# HyperRAM.net
KiCad netlist of a schematic drawn in Altium Designer
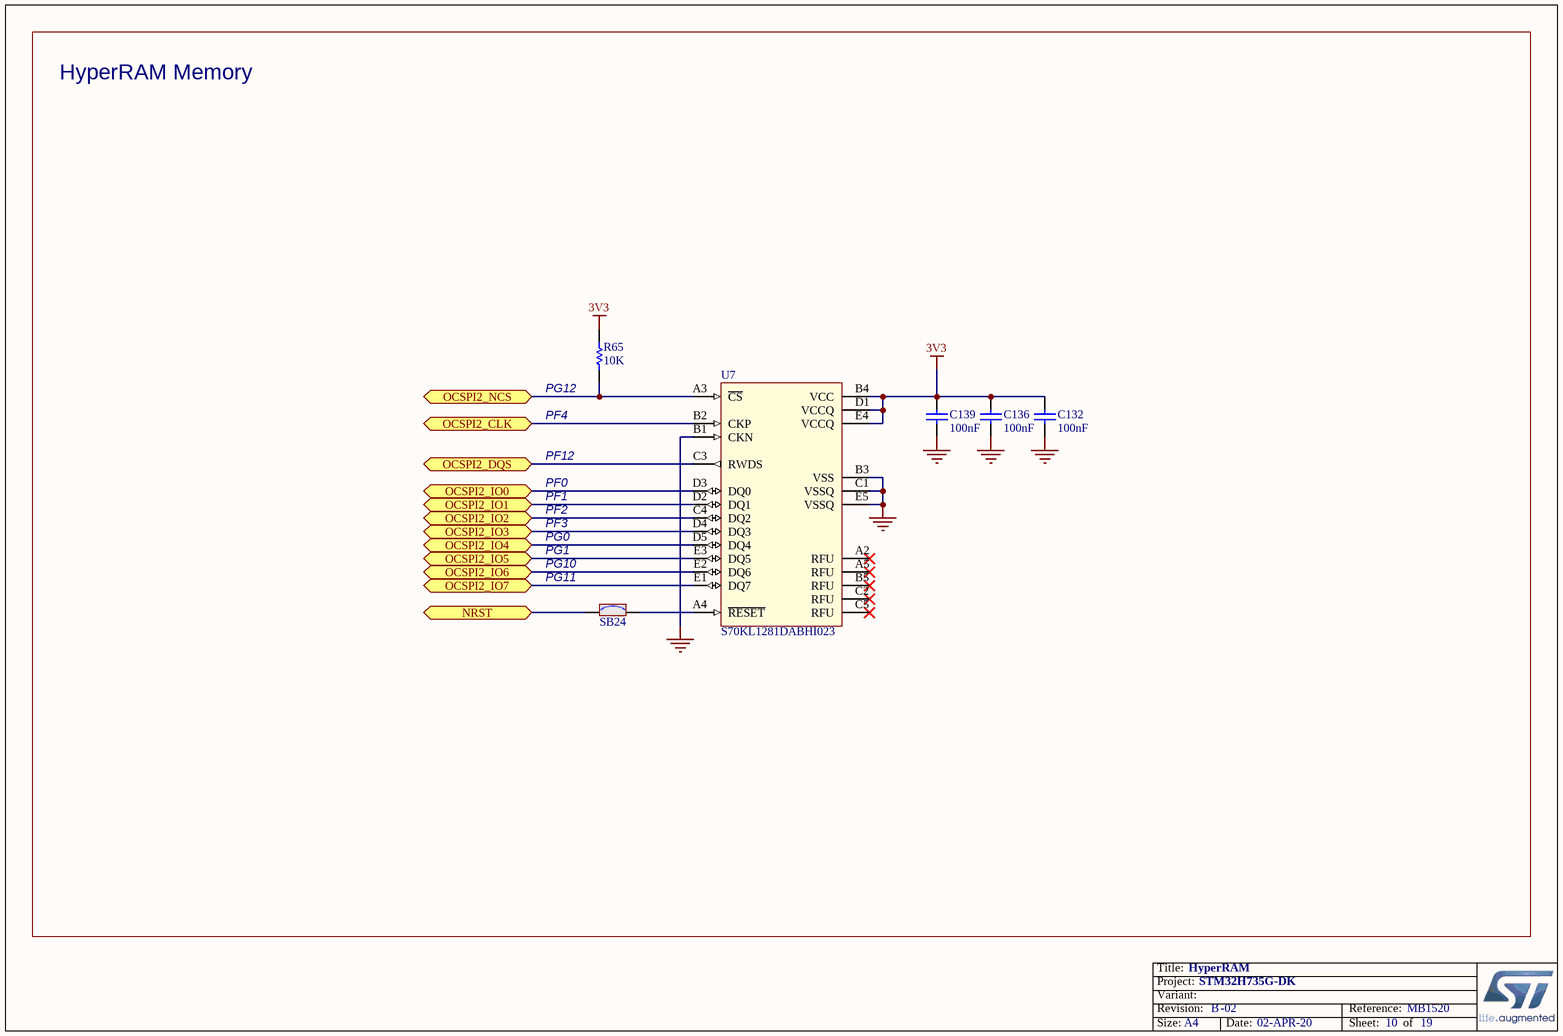
[diagram p0: HyperRAM.SchDoc]

(export (version "E")
  (design (tool "Eeschema 10.0.6"))
  (components
    (comp (ref "C132")
      (value "100nF")
      (footprint "C0402")
      (description "Capacitor, MLCC, 100nF, 16V, X7R, 10%, 0402, T=0,5mm")
      (fields
        (field (name "INTERNAL_PART_NUMBER") "MCD-00102")
        (field (name "MANUFACTURER_PART_NUMBER") "CC0402KRX7R7BB104")
        (field (name "PROVIDED_BY") "SUBCO")
      )
      (libsource (lib "MCD_PARTS_database") (part "Capacitor"))
    )
    (comp (ref "C136")
      (value "100nF")
      (footprint "C0402")
      (description "Capacitor, MLCC, 100nF, 16V, X7R, 10%, 0402, T=0,5mm")
      (fields
        (field (name "INTERNAL_PART_NUMBER") "MCD-00102")
        (field (name "MANUFACTURER_PART_NUMBER") "CC0402KRX7R7BB104")
        (field (name "PROVIDED_BY") "SUBCO")
      )
      (libsource (lib "MCD_PARTS_database") (part "Capacitor"))
    )
    (comp (ref "C139")
      (value "100nF")
      (footprint "C0402")
      (description "Capacitor, MLCC, 100nF, 16V, X7R, 10%, 0402, T=0,5mm")
      (fields
        (field (name "INTERNAL_PART_NUMBER") "MCD-00102")
        (field (name "MANUFACTURER_PART_NUMBER") "CC0402KRX7R7BB104")
        (field (name "PROVIDED_BY") "SUBCO")
      )
      (libsource (lib "MCD_PARTS_database") (part "Capacitor"))
    )
    (comp (ref "R65")
      (value "10K")
      (footprint "R0402")
      (description "Resistor,10K,0402,1%,1/16W")
      (fields
        (field (name "INTERNAL_PART_NUMBER") "MCD-00053")
        (field (name "MANUFACTURER_PART_NUMBER") "RC0402FR-0710KL")
        (field (name "PROVIDED_BY") "SUBCO")
      )
      (libsource (lib "MCD_PARTS_database") (part "Resistor"))
    )
    (comp (ref "SB24")
      (value "SB_ON")
      (footprint "SOLDER-BRIDGE_R0603-0R")
      (description "Solder Bridge ON")
      (fields
        (field (name "INTERNAL_PART_NUMBER") "MCD-00071")
        (field (name "MANUFACTURER_PART_NUMBER") "RC0603JR-070RL")
        (field (name "PROVIDED_BY") "SUBCO")
      )
      (libsource (lib "MCD_PARTS_database") (part "SB_ON"))
    )
    (comp (ref "U7")
      (value "S70KL1281DABHI023")
      (footprint "ICC_FBGA24_5X5-BALL-ARRAY_6X8_P1")
      (description "Memory, HyperRAM,128Mb,100MHz,3V,BGA24")
      (fields
        (field (name "INTERNAL_PART_NUMBER") "MCD-01824")
        (field (name "MANUFACTURER") "CYPRESS")
        (field (name "PROVIDED_BY") "SUBCO")
      )
      (libsource (lib "MCD_PARTS_database") (part "S70KL1281DABHI023"))
    )
  )
  (nets
    (net (code "1") (name "/NRST") (class "Default")
      (node (ref "SB24") (pin "1") (pinfunction "1_1") (pintype "passive"))
    )
    (net (code "2") (name "/OCSPI2_CLK") (class "Default")
      (node (ref "U7") (pin "B2") (pinfunction "CKP_B2") (pintype "input"))
    )
    (net (code "3") (name "/OCSPI2_DQS") (class "Default")
      (node (ref "U7") (pin "C3") (pinfunction "RWDS_C3") (pintype "output"))
    )
    (net (code "4") (name "/OCSPI2_IO0") (class "Default")
      (node (ref "U7") (pin "D3") (pinfunction "DQ0_D3") (pintype "bidirectional"))
    )
    (net (code "5") (name "/OCSPI2_IO1") (class "Default")
      (node (ref "U7") (pin "D2") (pinfunction "DQ1_D2") (pintype "bidirectional"))
    )
    (net (code "6") (name "/OCSPI2_IO2") (class "Default")
      (node (ref "U7") (pin "C4") (pinfunction "DQ2_C4") (pintype "bidirectional"))
    )
    (net (code "7") (name "/OCSPI2_IO3") (class "Default")
      (node (ref "U7") (pin "D4") (pinfunction "DQ3_D4") (pintype "bidirectional"))
    )
    (net (code "8") (name "/OCSPI2_IO4") (class "Default")
      (node (ref "U7") (pin "D5") (pinfunction "DQ4_D5") (pintype "bidirectional"))
    )
    (net (code "9") (name "/OCSPI2_IO5") (class "Default")
      (node (ref "U7") (pin "E3") (pinfunction "DQ5_E3") (pintype "bidirectional"))
    )
    (net (code "10") (name "/OCSPI2_IO6") (class "Default")
      (node (ref "U7") (pin "E2") (pinfunction "DQ6_E2") (pintype "bidirectional"))
    )
    (net (code "11") (name "/OCSPI2_IO7") (class "Default")
      (node (ref "U7") (pin "E1") (pinfunction "DQ7_E1") (pintype "bidirectional"))
    )
    (net (code "12") (name "/OCSPI2_NCS") (class "Default")
      (node (ref "R65") (pin "1") (pinfunction "1_1") (pintype "passive"))
      (node (ref "U7") (pin "A3") (pinfunction "~{CS}_A3") (pintype "input"))
    )
    (net (code "13") (name "3V3") (class "Default")
      (node (ref "C132") (pin "2") (pinfunction "2_2") (pintype "passive"))
      (node (ref "C136") (pin "2") (pinfunction "2_2") (pintype "passive"))
      (node (ref "C139") (pin "2") (pinfunction "2_2") (pintype "passive"))
      (node (ref "R65") (pin "2") (pinfunction "2_2") (pintype "passive"))
      (node (ref "U7") (pin "B4") (pinfunction "VCC_B4") (pintype "power_in"))
      (node (ref "U7") (pin "D1") (pinfunction "VCCQ_D1") (pintype "power_in"))
      (node (ref "U7") (pin "E4") (pinfunction "VCCQ_E4") (pintype "power_in"))
    )
    (net (code "14") (name "GND") (class "Default")
      (node (ref "C132") (pin "1") (pinfunction "1_1") (pintype "passive"))
      (node (ref "C136") (pin "1") (pinfunction "1_1") (pintype "passive"))
      (node (ref "C139") (pin "1") (pinfunction "1_1") (pintype "passive"))
      (node (ref "U7") (pin "B1") (pinfunction "CKN_B1") (pintype "input"))
      (node (ref "U7") (pin "B3") (pinfunction "VSS_B3") (pintype "power_in"))
      (node (ref "U7") (pin "C1") (pinfunction "VSSQ_C1") (pintype "power_in"))
      (node (ref "U7") (pin "E5") (pinfunction "VSSQ_E5") (pintype "power_in"))
    )
    (net (code "15") (name "Net-(U7-~{RESET})") (class "Default")
      (node (ref "SB24") (pin "2") (pinfunction "2_2") (pintype "passive"))
      (node (ref "U7") (pin "A4") (pinfunction "~{RESET}_A4") (pintype "input"))
    )
    (net (code "16") (name "unconnected-(U7-RFU-PadA2)") (class "Default")
      (node (ref "U7") (pin "A2") (pinfunction "RFU_A2") (pintype "power_in+no_connect"))
    )
    (net (code "17") (name "unconnected-(U7-RFU-PadA5)") (class "Default")
      (node (ref "U7") (pin "A5") (pinfunction "RFU_A5") (pintype "power_in+no_connect"))
    )
    (net (code "18") (name "unconnected-(U7-RFU-PadB5)") (class "Default")
      (node (ref "U7") (pin "B5") (pinfunction "RFU_B5") (pintype "power_in+no_connect"))
    )
    (net (code "19") (name "unconnected-(U7-RFU-PadC2)") (class "Default")
      (node (ref "U7") (pin "C2") (pinfunction "RFU_C2") (pintype "power_in+no_connect"))
    )
    (net (code "20") (name "unconnected-(U7-RFU-PadC5)") (class "Default")
      (node (ref "U7") (pin "C5") (pinfunction "RFU_C5") (pintype "power_in+no_connect"))
    )
  )
)
